# ConcentradorC.net
KiCad netlist of a schematic drawn in EAGLE
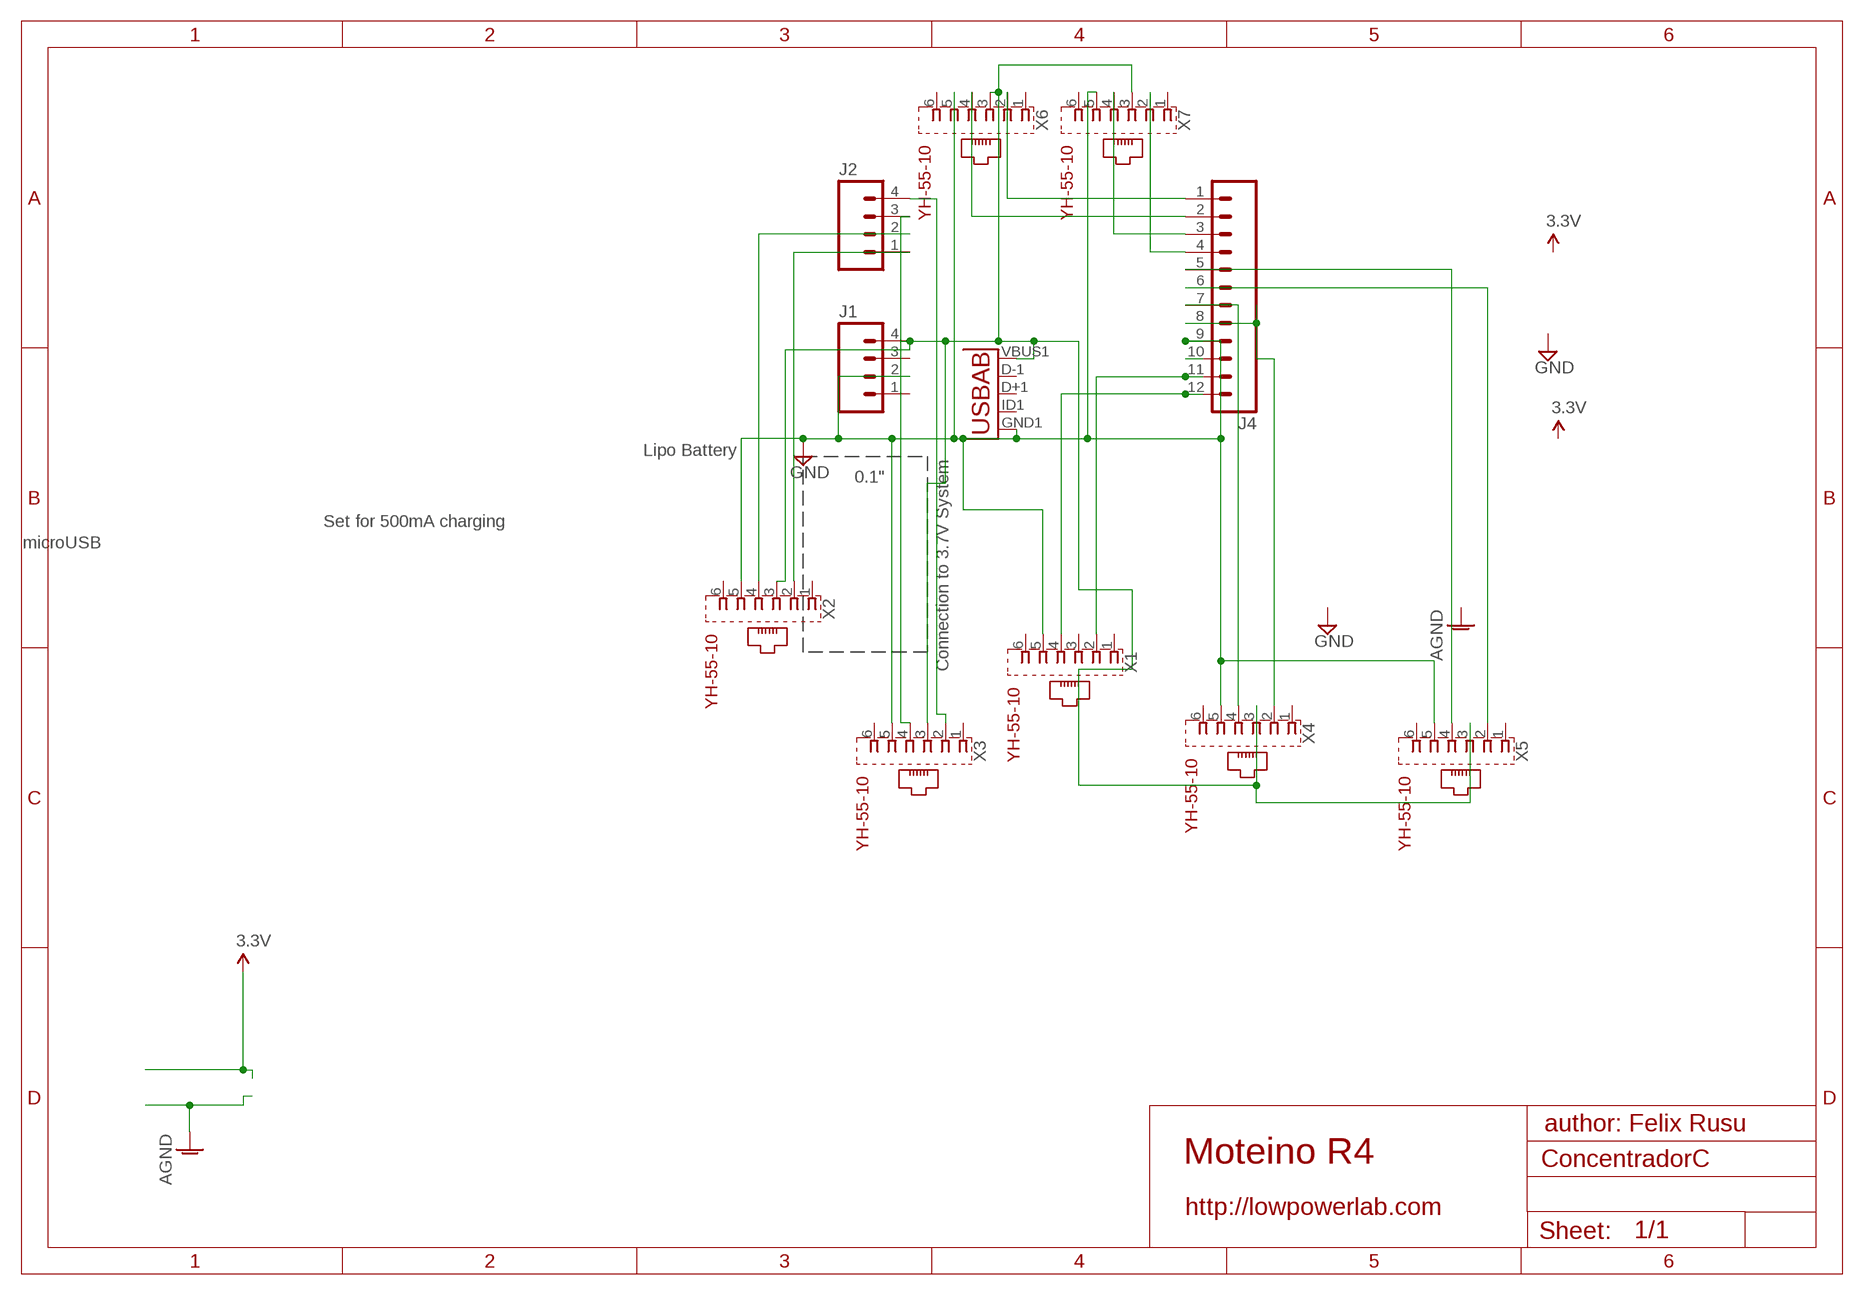
[diagram p0: schematic, sheet 1]

(export (version "E")
  (design (tool "Eeschema 10.0.6"))
  (components
    (comp (ref "J1")
      (value "M04PTH")
      (footprint "eagle-import:1X04")
      (libsource (lib "eagle-import") (part "M04PTH"))
    )
    (comp (ref "J2")
      (value "M04PTH")
      (footprint "eagle-import:1X04")
      (libsource (lib "eagle-import") (part "M04PTH"))
    )
    (comp (ref "J4")
      (value "M12PTH")
      (footprint "eagle-import:1X12")
      (libsource (lib "eagle-import") (part "M12PTH"))
    )
    (comp (ref "JP9")
      (value "Micro USB")
      (footprint "eagle-import:USB-AB-MICRO-SMD_V03")
      (libsource (lib "eagle-import") (part "USB-ABCONN-11794"))
    )
    (comp (ref "X1")
      (value "YH-55-10")
      (footprint "eagle-import:YH-55-10")
      (libsource (lib "eagle-import") (part "YH-55-10"))
    )
    (comp (ref "X2")
      (value "YH-55-10")
      (footprint "eagle-import:YH-55-10")
      (libsource (lib "eagle-import") (part "YH-55-10"))
    )
    (comp (ref "X3")
      (value "YH-55-10")
      (footprint "eagle-import:YH-55-10")
      (libsource (lib "eagle-import") (part "YH-55-10"))
    )
    (comp (ref "X4")
      (value "YH-55-10")
      (footprint "eagle-import:YH-55-10")
      (libsource (lib "eagle-import") (part "YH-55-10"))
    )
    (comp (ref "X5")
      (value "YH-55-10")
      (footprint "eagle-import:YH-55-10")
      (libsource (lib "eagle-import") (part "YH-55-10"))
    )
    (comp (ref "X6")
      (value "YH-55-10")
      (footprint "eagle-import:YH-55-10")
      (libsource (lib "eagle-import") (part "YH-55-10"))
    )
    (comp (ref "X7")
      (value "YH-55-10")
      (footprint "eagle-import:YH-55-10")
      (libsource (lib "eagle-import") (part "YH-55-10"))
    )
  )
  (nets
    (net (code "3") (name "GND") (class "Default")
      (node (ref "J1") (pin "2") (pinfunction "2_2") (pintype "passive"))
      (node (ref "J4") (pin "9") (pinfunction "9_9") (pintype "passive"))
      (node (ref "JP9") (pin "GND1") (pinfunction "GND_GND1") (pintype "bidirectional"))
      (node (ref "X1") (pin "5") (pinfunction "5_5") (pintype "passive"))
      (node (ref "X2") (pin "5") (pinfunction "5_5") (pintype "passive"))
      (node (ref "X3") (pin "5") (pinfunction "5_5") (pintype "passive"))
      (node (ref "X4") (pin "5") (pinfunction "5_5") (pintype "passive"))
      (node (ref "X5") (pin "5") (pinfunction "5_5") (pintype "passive"))
      (node (ref "X6") (pin "5") (pinfunction "5_5") (pintype "passive"))
      (node (ref "X7") (pin "5") (pinfunction "5_5") (pintype "passive"))
    )
    (net (code "4") (name "Net-(J2-Pad1)") (class "Default")
      (node (ref "J2") (pin "1") (pinfunction "1_1") (pintype "passive"))
      (node (ref "X2") (pin "2") (pinfunction "2_2") (pintype "passive"))
    )
    (net (code "5") (name "Net-(J2-Pad2)") (class "Default")
      (node (ref "J2") (pin "2") (pinfunction "2_2") (pintype "passive"))
      (node (ref "X2") (pin "4") (pinfunction "4_4") (pintype "passive"))
    )
    (net (code "6") (name "Net-(J2-Pad3)") (class "Default")
      (node (ref "J2") (pin "3") (pinfunction "3_3") (pintype "passive"))
      (node (ref "X3") (pin "4") (pinfunction "4_4") (pintype "passive"))
    )
    (net (code "7") (name "Net-(J2-Pad4)") (class "Default")
      (node (ref "J2") (pin "4") (pinfunction "4_4") (pintype "passive"))
      (node (ref "X3") (pin "2") (pinfunction "2_2") (pintype "passive"))
    )
    (net (code "8") (name "Net-(J4-Pad1)") (class "Default")
      (node (ref "J4") (pin "1") (pinfunction "1_1") (pintype "passive"))
      (node (ref "X6") (pin "2") (pinfunction "2_2") (pintype "passive"))
    )
    (net (code "9") (name "Net-(J4-Pad2)") (class "Default")
      (node (ref "J4") (pin "2") (pinfunction "2_2") (pintype "passive"))
      (node (ref "X6") (pin "4") (pinfunction "4_4") (pintype "passive"))
    )
    (net (code "10") (name "Net-(J4-Pad3)") (class "Default")
      (node (ref "J4") (pin "3") (pinfunction "3_3") (pintype "passive"))
      (node (ref "X7") (pin "4") (pinfunction "4_4") (pintype "passive"))
    )
    (net (code "11") (name "Net-(J4-Pad4)") (class "Default")
      (node (ref "J4") (pin "4") (pinfunction "4_4") (pintype "passive"))
      (node (ref "X7") (pin "2") (pinfunction "2_2") (pintype "passive"))
    )
    (net (code "12") (name "Net-(J4-Pad5)") (class "Default")
      (node (ref "J4") (pin "5") (pinfunction "5_5") (pintype "passive"))
      (node (ref "X5") (pin "4") (pinfunction "4_4") (pintype "passive"))
    )
    (net (code "13") (name "Net-(J4-Pad6)") (class "Default")
      (node (ref "J4") (pin "6") (pinfunction "6_6") (pintype "passive"))
      (node (ref "X5") (pin "2") (pinfunction "2_2") (pintype "passive"))
    )
    (net (code "14") (name "Net-(J4-Pad7)") (class "Default")
      (node (ref "J4") (pin "7") (pinfunction "7_7") (pintype "passive"))
      (node (ref "X4") (pin "4") (pinfunction "4_4") (pintype "passive"))
    )
    (net (code "15") (name "Net-(J4-Pad8)") (class "Default")
      (node (ref "J4") (pin "8") (pinfunction "8_8") (pintype "passive"))
      (node (ref "X4") (pin "2") (pinfunction "2_2") (pintype "passive"))
    )
    (net (code "16") (name "Net-(J4-Pad11)") (class "Default")
      (node (ref "J4") (pin "11") (pinfunction "11_11") (pintype "passive"))
      (node (ref "X1") (pin "2") (pinfunction "2_2") (pintype "passive"))
    )
    (net (code "17") (name "Net-(J4-Pad12)") (class "Default")
      (node (ref "J4") (pin "12") (pinfunction "12_12") (pintype "passive"))
      (node (ref "X1") (pin "4") (pinfunction "4_4") (pintype "passive"))
    )
    (net (code "18") (name "Net-(JP9-VBUS)") (class "Default")
      (node (ref "J1") (pin "4") (pinfunction "4_4") (pintype "passive"))
      (node (ref "JP9") (pin "VBUS1") (pinfunction "VBUS_VBUS1") (pintype "bidirectional"))
      (node (ref "X2") (pin "3") (pinfunction "3_3") (pintype "passive"))
      (node (ref "X3") (pin "3") (pinfunction "3_3") (pintype "passive"))
      (node (ref "X4") (pin "3") (pinfunction "3_3") (pintype "passive"))
      (node (ref "X5") (pin "3") (pinfunction "3_3") (pintype "passive"))
      (node (ref "X6") (pin "3") (pinfunction "3_3") (pintype "passive"))
      (node (ref "X7") (pin "3") (pinfunction "3_3") (pintype "passive"))
    )
    (net (code "19") (name "unconnected-(J1-Pad1)") (class "Default")
      (node (ref "J1") (pin "1") (pinfunction "1_1") (pintype "passive"))
    )
    (net (code "20") (name "unconnected-(J1-Pad3)") (class "Default")
      (node (ref "J1") (pin "3") (pinfunction "3_3") (pintype "passive"))
    )
    (net (code "21") (name "unconnected-(J4-Pad10)") (class "Default")
      (node (ref "J4") (pin "10") (pinfunction "10_10") (pintype "passive"))
    )
    (net (code "22") (name "unconnected-(JP9-D+-PadD+1)") (class "Default")
      (node (ref "JP9") (pin "D+1") (pinfunction "D+_D+1") (pintype "bidirectional"))
    )
    (net (code "23") (name "unconnected-(JP9-D--PadD-1)") (class "Default")
      (node (ref "JP9") (pin "D-1") (pinfunction "D-_D-1") (pintype "bidirectional"))
    )
    (net (code "24") (name "unconnected-(JP9-USBID-PadID1)") (class "Default")
      (node (ref "JP9") (pin "ID1") (pinfunction "USBID_ID1") (pintype "bidirectional"))
    )
    (net (code "25") (name "unconnected-(X1-Pad1)") (class "Default")
      (node (ref "X1") (pin "1") (pinfunction "1_1") (pintype "passive"))
    )
    (net (code "26") (name "unconnected-(X1-Pad3)") (class "Default")
      (node (ref "X1") (pin "3") (pinfunction "3_3") (pintype "passive"))
    )
    (net (code "27") (name "unconnected-(X1-Pad6)") (class "Default")
      (node (ref "X1") (pin "6") (pinfunction "6_6") (pintype "passive"))
    )
    (net (code "28") (name "unconnected-(X2-Pad1)") (class "Default")
      (node (ref "X2") (pin "1") (pinfunction "1_1") (pintype "passive"))
    )
    (net (code "29") (name "unconnected-(X2-Pad6)") (class "Default")
      (node (ref "X2") (pin "6") (pinfunction "6_6") (pintype "passive"))
    )
    (net (code "30") (name "unconnected-(X3-Pad1)") (class "Default")
      (node (ref "X3") (pin "1") (pinfunction "1_1") (pintype "passive"))
    )
    (net (code "31") (name "unconnected-(X3-Pad6)") (class "Default")
      (node (ref "X3") (pin "6") (pinfunction "6_6") (pintype "passive"))
    )
    (net (code "32") (name "unconnected-(X4-Pad1)") (class "Default")
      (node (ref "X4") (pin "1") (pinfunction "1_1") (pintype "passive"))
    )
    (net (code "33") (name "unconnected-(X4-Pad6)") (class "Default")
      (node (ref "X4") (pin "6") (pinfunction "6_6") (pintype "passive"))
    )
    (net (code "34") (name "unconnected-(X5-Pad1)") (class "Default")
      (node (ref "X5") (pin "1") (pinfunction "1_1") (pintype "passive"))
    )
    (net (code "35") (name "unconnected-(X5-Pad6)") (class "Default")
      (node (ref "X5") (pin "6") (pinfunction "6_6") (pintype "passive"))
    )
    (net (code "36") (name "unconnected-(X6-Pad1)") (class "Default")
      (node (ref "X6") (pin "1") (pinfunction "1_1") (pintype "passive"))
    )
    (net (code "37") (name "unconnected-(X6-Pad6)") (class "Default")
      (node (ref "X6") (pin "6") (pinfunction "6_6") (pintype "passive"))
    )
    (net (code "38") (name "unconnected-(X7-Pad1)") (class "Default")
      (node (ref "X7") (pin "1") (pinfunction "1_1") (pintype "passive"))
    )
    (net (code "39") (name "unconnected-(X7-Pad6)") (class "Default")
      (node (ref "X7") (pin "6") (pinfunction "6_6") (pintype "passive"))
    )
  )
)
